# 0763-graviton.net
KiCad netlist of a schematic drawn in EAGLE
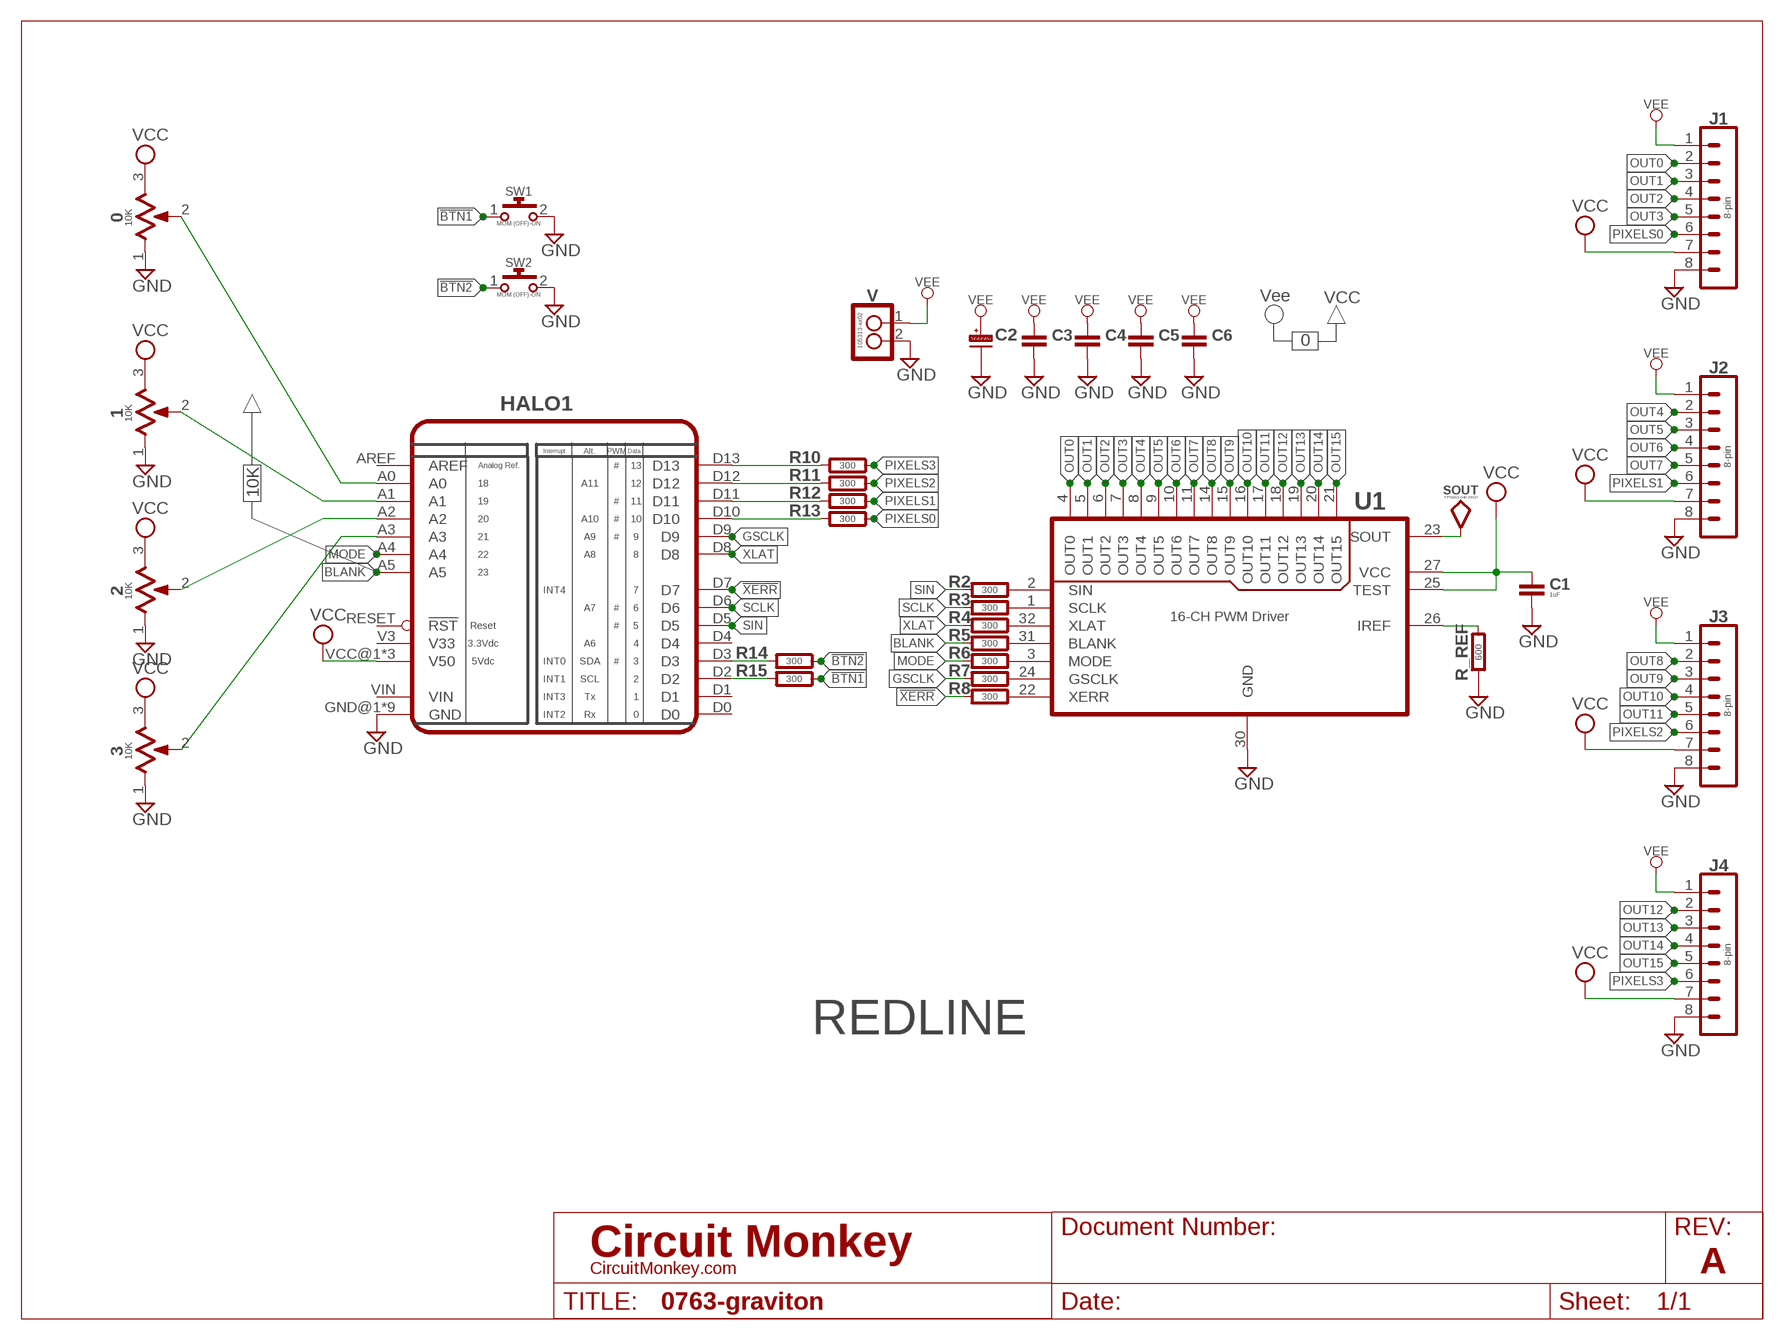
[diagram p0: schematic, sheet 1]

(export (version "E")
  (design (tool "Eeschema 10.0.6"))
  (components
    (comp (ref "0")
      (value "10K")
      (footprint "eagle-import:ALPS_RK09D113")
      (fields (field (name "MFR") "Alps") (field (name "MPN") "RK09D1130C1B"))
      (libsource (lib "eagle-import") (part "POTRK09?113"))
    )
    (comp (ref "1")
      (value "10K")
      (footprint "eagle-import:ALPS_RK09D113")
      (fields (field (name "MFR") "Alps") (field (name "MPN") "RK09D1130C1B"))
      (libsource (lib "eagle-import") (part "POTRK09?113"))
    )
    (comp (ref "2")
      (value "10K")
      (footprint "eagle-import:ALPS_RK09D113")
      (fields (field (name "MFR") "Alps") (field (name "MPN") "RK09D1130C1B"))
      (libsource (lib "eagle-import") (part "POTRK09?113"))
    )
    (comp (ref "3")
      (value "10K")
      (footprint "eagle-import:ALPS_RK09D113")
      (fields (field (name "MFR") "Alps") (field (name "MPN") "RK09D1130C1B"))
      (libsource (lib "eagle-import") (part "POTRK09?113"))
    )
    (comp (ref "C1")
      (value "1uF")
      (footprint "eagle-import:0603-CAP")
      (libsource (lib "eagle-import") (part "CAPACITOR0603"))
    )
    (comp (ref "C2")
      (value "CAPACITOR_POL-ALUM-SMT-10")
      (footprint "eagle-import:CAP_ALUM_SMT_10")
      (libsource (lib "eagle-import") (part "CAPACITOR_POL-ALUM-SMT-10"))
    )
    (comp (ref "C3")
      (value "CAPACITOR1210")
      (footprint "eagle-import:1210-CAP")
      (libsource (lib "eagle-import") (part "CAPACITOR1210"))
    )
    (comp (ref "C4")
      (value "CAPACITOR1210")
      (footprint "eagle-import:1210-CAP")
      (libsource (lib "eagle-import") (part "CAPACITOR1210"))
    )
    (comp (ref "C5")
      (value "CAPACITOR1210")
      (footprint "eagle-import:1210-CAP")
      (libsource (lib "eagle-import") (part "CAPACITOR1210"))
    )
    (comp (ref "C6")
      (value "CAPACITOR1210")
      (footprint "eagle-import:1210-CAP")
      (libsource (lib "eagle-import") (part "CAPACITOR1210"))
    )
    (comp (ref "HALO1")
      (value "HALO-A2")
      (footprint "eagle-import:PCB-HALO-A2-PINS")
      (libsource (lib "eagle-import") (part "HALO-A2"))
    )
    (comp (ref "J1")
      (value "8-pin")
      (footprint "eagle-import:B8B-PH-SM4")
      (fields (field (name "MFR") "JST") (field (name "MPN") "B8B-PH-SM4"))
      (libsource (lib "eagle-import") (part "08PPH-VT-SMD"))
    )
    (comp (ref "J2")
      (value "8-pin")
      (footprint "eagle-import:B8B-PH-SM4")
      (fields (field (name "MFR") "JST") (field (name "MPN") "B8B-PH-SM4"))
      (libsource (lib "eagle-import") (part "08PPH-VT-SMD"))
    )
    (comp (ref "J3")
      (value "8-pin")
      (footprint "eagle-import:B8B-PH-SM4")
      (fields (field (name "MFR") "JST") (field (name "MPN") "B8B-PH-SM4"))
      (libsource (lib "eagle-import") (part "08PPH-VT-SMD"))
    )
    (comp (ref "J4")
      (value "8-pin")
      (footprint "eagle-import:B8B-PH-SM4")
      (fields (field (name "MFR") "JST") (field (name "MPN") "B8B-PH-SM4"))
      (libsource (lib "eagle-import") (part "08PPH-VT-SMD"))
    )
    (comp (ref "R2")
      (value "300")
      (footprint "eagle-import:0603-RES")
      (libsource (lib "eagle-import") (part "RESISTOR0603"))
    )
    (comp (ref "R3")
      (value "300")
      (footprint "eagle-import:0603-RES")
      (libsource (lib "eagle-import") (part "RESISTOR0603"))
    )
    (comp (ref "R4")
      (value "300")
      (footprint "eagle-import:0603-RES")
      (libsource (lib "eagle-import") (part "RESISTOR0603"))
    )
    (comp (ref "R5")
      (value "300")
      (footprint "eagle-import:0603-RES")
      (libsource (lib "eagle-import") (part "RESISTOR0603"))
    )
    (comp (ref "R6")
      (value "300")
      (footprint "eagle-import:0603-RES")
      (libsource (lib "eagle-import") (part "RESISTOR0603"))
    )
    (comp (ref "R7")
      (value "300")
      (footprint "eagle-import:0603-RES")
      (libsource (lib "eagle-import") (part "RESISTOR0603"))
    )
    (comp (ref "R8")
      (value "300")
      (footprint "eagle-import:0603-RES")
      (libsource (lib "eagle-import") (part "RESISTOR0603"))
    )
    (comp (ref "R10")
      (value "300")
      (footprint "eagle-import:0603-RES")
      (libsource (lib "eagle-import") (part "RESISTOR0603"))
    )
    (comp (ref "R11")
      (value "300")
      (footprint "eagle-import:0603-RES")
      (libsource (lib "eagle-import") (part "RESISTOR0603"))
    )
    (comp (ref "R12")
      (value "300")
      (footprint "eagle-import:0603-RES")
      (libsource (lib "eagle-import") (part "RESISTOR0603"))
    )
    (comp (ref "R13")
      (value "300")
      (footprint "eagle-import:0603-RES")
      (libsource (lib "eagle-import") (part "RESISTOR0603"))
    )
    (comp (ref "R14")
      (value "300")
      (footprint "eagle-import:0603-RES")
      (libsource (lib "eagle-import") (part "RESISTOR0603"))
    )
    (comp (ref "R15")
      (value "300")
      (footprint "eagle-import:0603-RES")
      (libsource (lib "eagle-import") (part "RESISTOR0603"))
    )
    (comp (ref "R_REF")
      (value "600")
      (footprint "eagle-import:0603-RES")
      (libsource (lib "eagle-import") (part "RESISTOR0603"))
    )
    (comp (ref "SOUT")
      (value "TPSMD-040-RND")
      (footprint "eagle-import:SMD-040MIL-RND")
      (libsource (lib "eagle-import") (part "TPSMD-040-RND"))
    )
    (comp (ref "SW1")
      (value "MOM (OFF)-ON")
      (footprint "eagle-import:SWITCH-0635-2P-SMD")
      (fields (field (name "MFR") "CK Switch") (field (name "MPN") "PTS635S*SMTR"))
      (libsource (lib "eagle-import") (part "TACTILE-2PSMD"))
    )
    (comp (ref "SW2")
      (value "MOM (OFF)-ON")
      (footprint "eagle-import:SWITCH-0635-2P-SMD")
      (fields (field (name "MFR") "CK Switch") (field (name "MPN") "PTS635S*SMTR"))
      (libsource (lib "eagle-import") (part "TACTILE-2PSMD"))
    )
    (comp (ref "U1")
      (value "16-CH PWM Driver")
      (footprint "eagle-import:QFN-32")
      (fields (field (name "MFR") "Texas Instruments") (field (name "MPN") "TLC59401RHB"))
      (libsource (lib "eagle-import") (part "TLC59401-QFN"))
    )
    (comp (ref "V")
      (value "105313-xx02")
      (footprint "eagle-import:MOLEX-105313-XX02")
      (libsource (lib "eagle-import") (part "NANOFIT-02P-SR"))
    )
  )
  (nets
    (net (code "1") (name "/~{BTN1}") (class "Default")
      (node (ref "R15") (pin "1") (pinfunction "1_1") (pintype "passive"))
      (node (ref "SW1") (pin "1") (pinfunction "1_1") (pintype "bidirectional"))
    )
    (net (code "2") (name "/~{BTN2}") (class "Default")
      (node (ref "R14") (pin "1") (pinfunction "1_1") (pintype "passive"))
      (node (ref "SW2") (pin "1") (pinfunction "1_1") (pintype "bidirectional"))
    )
    (net (code "3") (name "/~{XERR}") (class "Default")
      (node (ref "HALO1") (pin "D7") (pinfunction "D7_D7") (pintype "bidirectional"))
      (node (ref "R8") (pin "2") (pinfunction "2_2") (pintype "passive"))
    )
    (net (code "4") (name "BLANK") (class "Default")
      (node (ref "HALO1") (pin "A5") (pinfunction "A5_A5") (pintype "bidirectional"))
      (node (ref "R5") (pin "2") (pinfunction "2_2") (pintype "passive"))
    )
    (net (code "5") (name "GND") (class "Default")
      (node (ref "0") (pin "1") (pinfunction "1_1") (pintype "passive"))
      (node (ref "1") (pin "1") (pinfunction "1_1") (pintype "passive"))
      (node (ref "2") (pin "1") (pinfunction "1_1") (pintype "passive"))
      (node (ref "3") (pin "1") (pinfunction "1_1") (pintype "passive"))
      (node (ref "C1") (pin "2") (pinfunction "2_2") (pintype "passive"))
      (node (ref "C2") (pin "-") (pinfunction "N_-") (pintype "bidirectional"))
      (node (ref "C3") (pin "2") (pinfunction "2_2") (pintype "passive"))
      (node (ref "C4") (pin "2") (pinfunction "2_2") (pintype "passive"))
      (node (ref "C5") (pin "2") (pinfunction "2_2") (pintype "passive"))
      (node (ref "C6") (pin "2") (pinfunction "2_2") (pintype "passive"))
      (node (ref "HALO1") (pin "GND@1") (pinfunction "GND_GND@1") (pintype "bidirectional"))
      (node (ref "HALO1") (pin "GND@1.2") (pinfunction "GND_GND@1.2") (pintype "bidirectional"))
      (node (ref "HALO1") (pin "GND@2") (pinfunction "GND_GND@2") (pintype "bidirectional"))
      (node (ref "HALO1") (pin "GND@3") (pinfunction "GND_GND@3") (pintype "bidirectional"))
      (node (ref "HALO1") (pin "GND@4") (pinfunction "GND_GND@4") (pintype "bidirectional"))
      (node (ref "HALO1") (pin "MTG1") (pinfunction "GND_MTG1") (pintype "bidirectional"))
      (node (ref "HALO1") (pin "MTG2") (pinfunction "GND_MTG2") (pintype "bidirectional"))
      (node (ref "HALO1") (pin "MTG3") (pinfunction "GND_MTG3") (pintype "bidirectional"))
      (node (ref "HALO1") (pin "MTG4") (pinfunction "GND_MTG4") (pintype "bidirectional"))
      (node (ref "J1") (pin "8") (pinfunction "8_8") (pintype "passive"))
      (node (ref "J2") (pin "8") (pinfunction "8_8") (pintype "passive"))
      (node (ref "J3") (pin "8") (pinfunction "8_8") (pintype "passive"))
      (node (ref "J4") (pin "8") (pinfunction "8_8") (pintype "passive"))
      (node (ref "R_REF") (pin "1") (pinfunction "1_1") (pintype "passive"))
      (node (ref "SW1") (pin "2") (pinfunction "2_2") (pintype "bidirectional"))
      (node (ref "SW2") (pin "2") (pinfunction "2_2") (pintype "bidirectional"))
      (node (ref "U1") (pin "30") (pinfunction "GND_30") (pintype "power_in"))
      (node (ref "V") (pin "2") (pinfunction "2_2") (pintype "bidirectional"))
    )
    (net (code "6") (name "GSCLK") (class "Default")
      (node (ref "HALO1") (pin "D9") (pinfunction "D9_D9") (pintype "bidirectional"))
      (node (ref "R7") (pin "2") (pinfunction "2_2") (pintype "passive"))
    )
    (net (code "7") (name "MODE") (class "Default")
      (node (ref "HALO1") (pin "A4") (pinfunction "A4_A4") (pintype "bidirectional"))
      (node (ref "R6") (pin "2") (pinfunction "2_2") (pintype "passive"))
    )
    (net (code "8") (name "Net-(0-Pad2)") (class "Default")
      (node (ref "0") (pin "2") (pinfunction "2_2") (pintype "passive"))
      (node (ref "HALO1") (pin "A0") (pinfunction "A0_A0") (pintype "bidirectional"))
    )
    (net (code "9") (name "Net-(1-Pad2)") (class "Default")
      (node (ref "1") (pin "2") (pinfunction "2_2") (pintype "passive"))
      (node (ref "HALO1") (pin "A1") (pinfunction "A1_A1") (pintype "bidirectional"))
    )
    (net (code "10") (name "Net-(2-Pad2)") (class "Default")
      (node (ref "2") (pin "2") (pinfunction "2_2") (pintype "passive"))
      (node (ref "HALO1") (pin "A2") (pinfunction "A2_A2") (pintype "bidirectional"))
    )
    (net (code "11") (name "Net-(3-Pad2)") (class "Default")
      (node (ref "3") (pin "2") (pinfunction "2_2") (pintype "passive"))
      (node (ref "HALO1") (pin "A3") (pinfunction "A3_A3") (pintype "bidirectional"))
    )
    (net (code "12") (name "Net-(HALO1-PadD2)") (class "Default")
      (node (ref "HALO1") (pin "D2") (pinfunction "D2_D2") (pintype "bidirectional"))
      (node (ref "R15") (pin "2") (pinfunction "2_2") (pintype "passive"))
    )
    (net (code "13") (name "Net-(HALO1-PadD3)") (class "Default")
      (node (ref "HALO1") (pin "D3") (pinfunction "D3_D3") (pintype "bidirectional"))
      (node (ref "R14") (pin "2") (pinfunction "2_2") (pintype "passive"))
    )
    (net (code "14") (name "Net-(HALO1-PadD10)") (class "Default")
      (node (ref "HALO1") (pin "D10") (pinfunction "D10_D10") (pintype "bidirectional"))
      (node (ref "R13") (pin "2") (pinfunction "2_2") (pintype "passive"))
    )
    (net (code "15") (name "Net-(HALO1-PadD11)") (class "Default")
      (node (ref "HALO1") (pin "D11") (pinfunction "D11_D11") (pintype "bidirectional"))
      (node (ref "R12") (pin "2") (pinfunction "2_2") (pintype "passive"))
    )
    (net (code "16") (name "Net-(HALO1-PadD12)") (class "Default")
      (node (ref "HALO1") (pin "D12") (pinfunction "D12_D12") (pintype "bidirectional"))
      (node (ref "R11") (pin "2") (pinfunction "2_2") (pintype "passive"))
    )
    (net (code "17") (name "Net-(HALO1-PadD13)") (class "Default")
      (node (ref "HALO1") (pin "D13") (pinfunction "D13_D13") (pintype "bidirectional"))
      (node (ref "R10") (pin "2") (pinfunction "2_2") (pintype "passive"))
    )
    (net (code "18") (name "Net-(SOUT-P$1)") (class "Default")
      (node (ref "SOUT") (pin "TP") (pinfunction "P$1_TP") (pintype "bidirectional"))
      (node (ref "U1") (pin "23") (pinfunction "SOUT_23") (pintype "output"))
    )
    (net (code "19") (name "Net-(U1-BLANK)") (class "Default")
      (node (ref "R5") (pin "1") (pinfunction "1_1") (pintype "passive"))
      (node (ref "U1") (pin "31") (pinfunction "BLANK_31") (pintype "input"))
    )
    (net (code "20") (name "Net-(U1-GSCLK)") (class "Default")
      (node (ref "R7") (pin "1") (pinfunction "1_1") (pintype "passive"))
      (node (ref "U1") (pin "24") (pinfunction "GSCLK_24") (pintype "input"))
    )
    (net (code "21") (name "Net-(U1-IREF)") (class "Default")
      (node (ref "R_REF") (pin "2") (pinfunction "2_2") (pintype "passive"))
      (node (ref "U1") (pin "26") (pinfunction "IREF_26") (pintype "passive"))
    )
    (net (code "22") (name "Net-(U1-MODE)") (class "Default")
      (node (ref "R6") (pin "1") (pinfunction "1_1") (pintype "passive"))
      (node (ref "U1") (pin "3") (pinfunction "MODE_3") (pintype "input"))
    )
    (net (code "23") (name "Net-(U1-SCLK)") (class "Default")
      (node (ref "R3") (pin "1") (pinfunction "1_1") (pintype "passive"))
      (node (ref "U1") (pin "1") (pinfunction "SCLK_1") (pintype "input"))
    )
    (net (code "24") (name "Net-(U1-SIN)") (class "Default")
      (node (ref "R2") (pin "1") (pinfunction "1_1") (pintype "passive"))
      (node (ref "U1") (pin "2") (pinfunction "SIN_2") (pintype "input"))
    )
    (net (code "25") (name "Net-(U1-XERR)") (class "Default")
      (node (ref "R8") (pin "1") (pinfunction "1_1") (pintype "passive"))
      (node (ref "U1") (pin "22") (pinfunction "XERR_22") (pintype "output"))
    )
    (net (code "26") (name "Net-(U1-XLAT)") (class "Default")
      (node (ref "R4") (pin "1") (pinfunction "1_1") (pintype "passive"))
      (node (ref "U1") (pin "32") (pinfunction "XLAT_32") (pintype "input"))
    )
    (net (code "27") (name "OUT0") (class "Default")
      (node (ref "J1") (pin "2") (pinfunction "2_2") (pintype "passive"))
      (node (ref "U1") (pin "4") (pinfunction "OUT0_4") (pintype "open_collector"))
    )
    (net (code "28") (name "OUT1") (class "Default")
      (node (ref "J1") (pin "3") (pinfunction "3_3") (pintype "passive"))
      (node (ref "U1") (pin "5") (pinfunction "OUT1_5") (pintype "open_collector"))
    )
    (net (code "29") (name "OUT2") (class "Default")
      (node (ref "J1") (pin "4") (pinfunction "4_4") (pintype "passive"))
      (node (ref "U1") (pin "6") (pinfunction "OUT2_6") (pintype "open_collector"))
    )
    (net (code "30") (name "OUT3") (class "Default")
      (node (ref "J1") (pin "5") (pinfunction "5_5") (pintype "passive"))
      (node (ref "U1") (pin "7") (pinfunction "OUT3_7") (pintype "open_collector"))
    )
    (net (code "31") (name "OUT4") (class "Default")
      (node (ref "J2") (pin "2") (pinfunction "2_2") (pintype "passive"))
      (node (ref "U1") (pin "8") (pinfunction "OUT4_8") (pintype "open_collector"))
    )
    (net (code "32") (name "OUT5") (class "Default")
      (node (ref "J2") (pin "3") (pinfunction "3_3") (pintype "passive"))
      (node (ref "U1") (pin "9") (pinfunction "OUT5_9") (pintype "open_collector"))
    )
    (net (code "33") (name "OUT6") (class "Default")
      (node (ref "J2") (pin "4") (pinfunction "4_4") (pintype "passive"))
      (node (ref "U1") (pin "10") (pinfunction "OUT6_10") (pintype "open_collector"))
    )
    (net (code "34") (name "OUT7") (class "Default")
      (node (ref "J2") (pin "5") (pinfunction "5_5") (pintype "passive"))
      (node (ref "U1") (pin "11") (pinfunction "OUT7_11") (pintype "open_collector"))
    )
    (net (code "35") (name "OUT8") (class "Default")
      (node (ref "J3") (pin "2") (pinfunction "2_2") (pintype "passive"))
      (node (ref "U1") (pin "14") (pinfunction "OUT8_14") (pintype "open_collector"))
    )
    (net (code "36") (name "OUT9") (class "Default")
      (node (ref "J3") (pin "3") (pinfunction "3_3") (pintype "passive"))
      (node (ref "U1") (pin "15") (pinfunction "OUT9_15") (pintype "open_collector"))
    )
    (net (code "37") (name "OUT10") (class "Default")
      (node (ref "J3") (pin "4") (pinfunction "4_4") (pintype "passive"))
      (node (ref "U1") (pin "16") (pinfunction "OUT10_16") (pintype "open_collector"))
    )
    (net (code "38") (name "OUT11") (class "Default")
      (node (ref "J3") (pin "5") (pinfunction "5_5") (pintype "passive"))
      (node (ref "U1") (pin "17") (pinfunction "OUT11_17") (pintype "open_collector"))
    )
    (net (code "39") (name "OUT12") (class "Default")
      (node (ref "J4") (pin "2") (pinfunction "2_2") (pintype "passive"))
      (node (ref "U1") (pin "18") (pinfunction "OUT12_18") (pintype "open_collector"))
    )
    (net (code "40") (name "OUT13") (class "Default")
      (node (ref "J4") (pin "3") (pinfunction "3_3") (pintype "passive"))
      (node (ref "U1") (pin "19") (pinfunction "OUT13_19") (pintype "open_collector"))
    )
    (net (code "41") (name "OUT14") (class "Default")
      (node (ref "J4") (pin "4") (pinfunction "4_4") (pintype "passive"))
      (node (ref "U1") (pin "20") (pinfunction "OUT14_20") (pintype "open_collector"))
    )
    (net (code "42") (name "OUT15") (class "Default")
      (node (ref "J4") (pin "5") (pinfunction "5_5") (pintype "passive"))
      (node (ref "U1") (pin "21") (pinfunction "OUT15_21") (pintype "open_collector"))
    )
    (net (code "43") (name "PIXELS0") (class "Default")
      (node (ref "J1") (pin "6") (pinfunction "6_6") (pintype "passive"))
      (node (ref "R13") (pin "1") (pinfunction "1_1") (pintype "passive"))
    )
    (net (code "44") (name "PIXELS1") (class "Default")
      (node (ref "J2") (pin "6") (pinfunction "6_6") (pintype "passive"))
      (node (ref "R12") (pin "1") (pinfunction "1_1") (pintype "passive"))
    )
    (net (code "45") (name "PIXELS2") (class "Default")
      (node (ref "J3") (pin "6") (pinfunction "6_6") (pintype "passive"))
      (node (ref "R11") (pin "1") (pinfunction "1_1") (pintype "passive"))
    )
    (net (code "46") (name "PIXELS3") (class "Default")
      (node (ref "J4") (pin "6") (pinfunction "6_6") (pintype "passive"))
      (node (ref "R10") (pin "1") (pinfunction "1_1") (pintype "passive"))
    )
    (net (code "47") (name "SCLK") (class "Default")
      (node (ref "HALO1") (pin "D6") (pinfunction "D6_D6") (pintype "bidirectional"))
      (node (ref "R3") (pin "2") (pinfunction "2_2") (pintype "passive"))
    )
    (net (code "48") (name "SIN") (class "Default")
      (node (ref "HALO1") (pin "D5") (pinfunction "D5_D5") (pintype "bidirectional"))
      (node (ref "R2") (pin "2") (pinfunction "2_2") (pintype "passive"))
    )
    (net (code "49") (name "VCC") (class "Default")
      (node (ref "0") (pin "3") (pinfunction "3_3") (pintype "passive"))
      (node (ref "1") (pin "3") (pinfunction "3_3") (pintype "passive"))
      (node (ref "2") (pin "3") (pinfunction "3_3") (pintype "passive"))
      (node (ref "3") (pin "3") (pinfunction "3_3") (pintype "passive"))
      (node (ref "C1") (pin "1") (pinfunction "1_1") (pintype "passive"))
      (node (ref "HALO1") (pin "VCC@1") (pinfunction "V50_VCC@1") (pintype "bidirectional"))
      (node (ref "HALO1") (pin "VCC@2") (pinfunction "V50_VCC@2") (pintype "bidirectional"))
      (node (ref "HALO1") (pin "VCC@3") (pinfunction "V50_VCC@3") (pintype "bidirectional"))
      (node (ref "J1") (pin "7") (pinfunction "7_7") (pintype "passive"))
      (node (ref "J2") (pin "7") (pinfunction "7_7") (pintype "passive"))
      (node (ref "J3") (pin "7") (pinfunction "7_7") (pintype "passive"))
      (node (ref "J4") (pin "7") (pinfunction "7_7") (pintype "passive"))
      (node (ref "U1") (pin "25") (pinfunction "TEST_25") (pintype "input"))
      (node (ref "U1") (pin "27") (pinfunction "VCC_27") (pintype "power_in"))
    )
    (net (code "50") (name "VEE") (class "Default")
      (node (ref "C2") (pin "+") (pinfunction "P_+") (pintype "bidirectional"))
      (node (ref "C3") (pin "1") (pinfunction "1_1") (pintype "passive"))
      (node (ref "C4") (pin "1") (pinfunction "1_1") (pintype "passive"))
      (node (ref "C5") (pin "1") (pinfunction "1_1") (pintype "passive"))
      (node (ref "C6") (pin "1") (pinfunction "1_1") (pintype "passive"))
      (node (ref "J1") (pin "1") (pinfunction "1_1") (pintype "passive"))
      (node (ref "J2") (pin "1") (pinfunction "1_1") (pintype "passive"))
      (node (ref "J3") (pin "1") (pinfunction "1_1") (pintype "passive"))
      (node (ref "J4") (pin "1") (pinfunction "1_1") (pintype "passive"))
      (node (ref "V") (pin "1") (pinfunction "1_1") (pintype "bidirectional"))
    )
    (net (code "51") (name "XLAT") (class "Default")
      (node (ref "HALO1") (pin "D8") (pinfunction "D8_D8") (pintype "bidirectional"))
      (node (ref "R4") (pin "2") (pinfunction "2_2") (pintype "passive"))
    )
    (net (code "52") (name "unconnected-(HALO1-PadAREF)") (class "Default")
      (node (ref "HALO1") (pin "AREF") (pinfunction "AREF_AREF") (pintype "bidirectional"))
    )
    (net (code "53") (name "unconnected-(HALO1-PadD0)") (class "Default")
      (node (ref "HALO1") (pin "D0") (pinfunction "D0_D0") (pintype "bidirectional"))
    )
    (net (code "54") (name "unconnected-(HALO1-PadD1)") (class "Default")
      (node (ref "HALO1") (pin "D1") (pinfunction "D1_D1") (pintype "bidirectional"))
    )
    (net (code "55") (name "unconnected-(HALO1-PadD4)") (class "Default")
      (node (ref "HALO1") (pin "D4") (pinfunction "D4_D4") (pintype "bidirectional"))
    )
    (net (code "56") (name "unconnected-(HALO1-PadVIN)") (class "Default")
      (node (ref "HALO1") (pin "VIN") (pinfunction "VIN_VIN") (pintype "bidirectional"))
    )
    (net (code "57") (name "unconnected-(HALO1-V33-PadV3)") (class "Default")
      (node (ref "HALO1") (pin "V3") (pinfunction "V33_V3") (pintype "bidirectional"))
    )
    (net (code "58") (name "unconnected-(HALO1-~{RST}-PadRESET)") (class "Default")
      (node (ref "HALO1") (pin "RESET") (pinfunction "~{RST}_RESET") (pintype "bidirectional"))
    )
  )
)
